# battery-select.net
KiCad netlist of a schematic drawn in Altium Designer
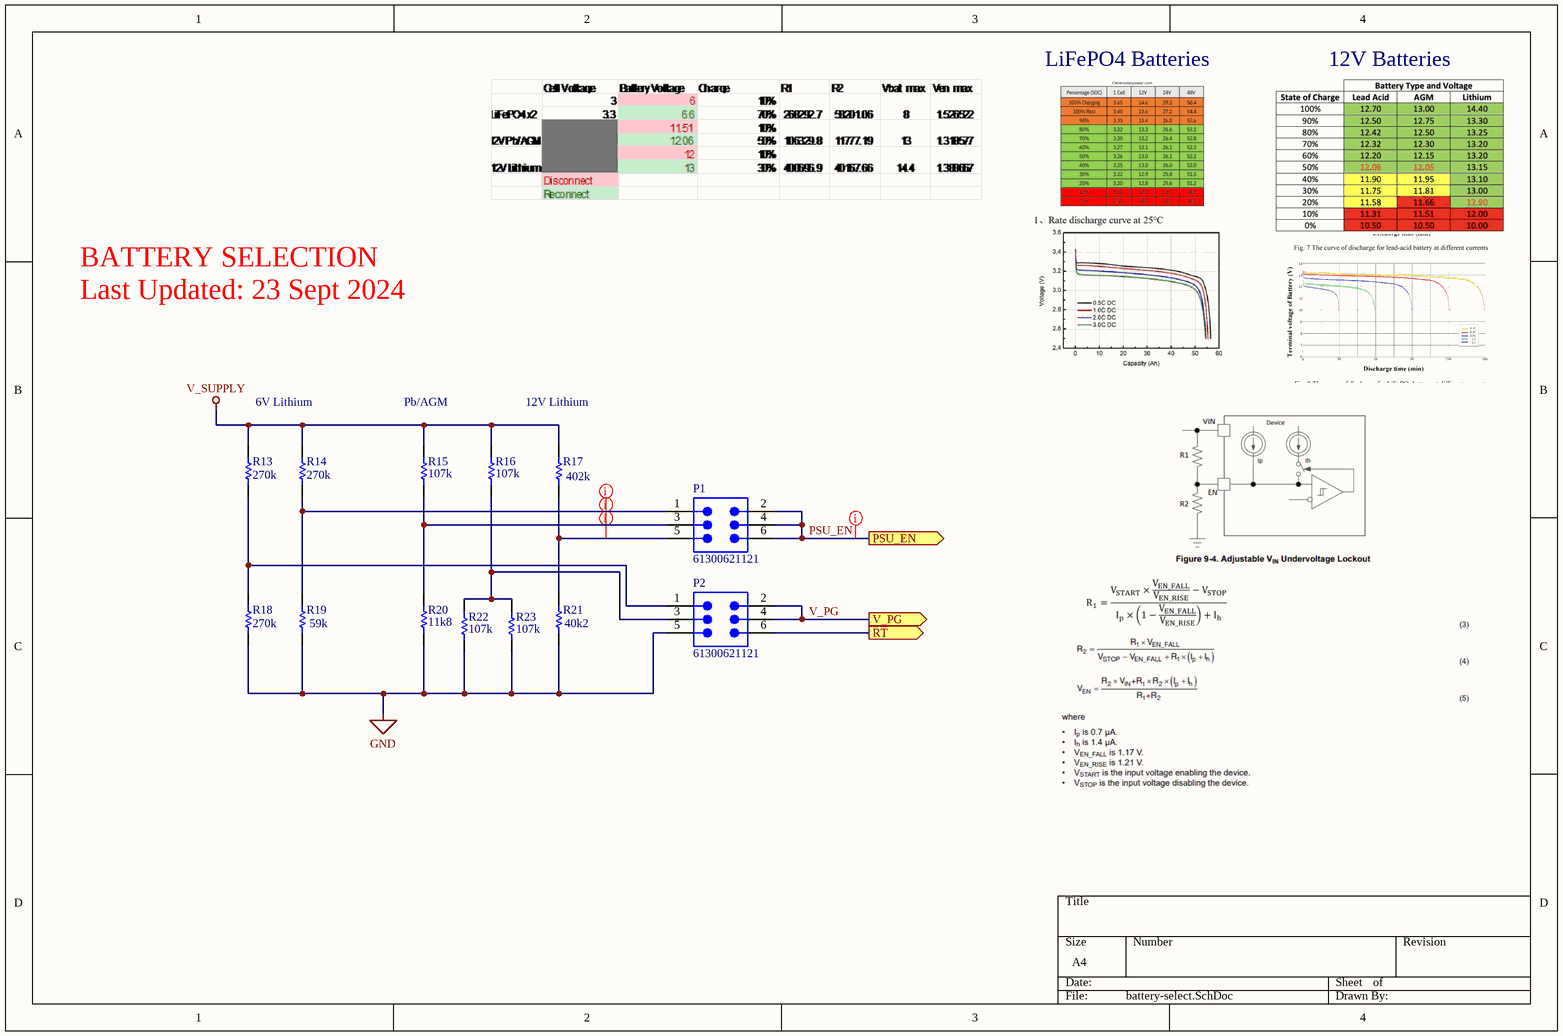
[diagram p0: battery-select.SchDoc]

(export (version "E")
  (design (tool "Eeschema 10.0.6"))
  (components
    (comp (ref "P1")
      (value "61300621121")
      (footprint "61300621121")
      (libsource (lib "Camosun College") (part "Header_Male_2R_06P"))
    )
    (comp (ref "P2")
      (value "61300621121")
      (footprint "61300621121")
      (libsource (lib "Camosun College") (part "Header_Male_2R_06P"))
    )
    (comp (ref "R13")
      (value "270k")
      (footprint "RESC2013X70X40LL20T20")
      (fields (field (name "PART NUMBER") "ERJ6ENF2703V") (field (name "MANUFACTURER") "Panasonic"))
      (libsource (lib "Altium Content Vault") (part "RES"))
    )
    (comp (ref "R14")
      (value "270k")
      (footprint "RESC2013X70X40LL20T20")
      (fields (field (name "PART NUMBER") "ERJ6ENF2703V") (field (name "MANUFACTURER") "Panasonic"))
      (libsource (lib "Altium Content Vault") (part "RES"))
    )
    (comp (ref "R15")
      (value "107k")
      (footprint "RESC2013X70X40LL20T20")
      (fields (field (name "MANUFACTURER") "Panasonic") (field (name "PART NUMBER") "ERJ-6ENF1073V"))
      (libsource (lib "Altium Content Vault") (part "RES"))
    )
    (comp (ref "R16")
      (value "107k")
      (footprint "RESC2013X70X40LL20T20")
      (fields (field (name "MANUFACTURER") "Panasonic") (field (name "PART NUMBER") "ERJ-6ENF1073V"))
      (libsource (lib "Altium Content Vault") (part "RES"))
    )
    (comp (ref "R17")
      (value "402k")
      (footprint "RESC2013X70X40LL20T20")
      (fields (field (name "PART NUMBER") "ERJ-6ENF4023V") (field (name "MANUFACTURER") "Panasonic"))
      (libsource (lib "Altium Content Vault") (part "RES"))
    )
    (comp (ref "R18")
      (value "270k")
      (footprint "RESC2013X70X40LL20T20")
      (fields (field (name "PART NUMBER") "ERJ6ENF2703V") (field (name "MANUFACTURER") "Panasonic"))
      (libsource (lib "Altium Content Vault") (part "RES"))
    )
    (comp (ref "R19")
      (value "59k")
      (footprint "RESC2013X70X40LL20T20")
      (fields (field (name "MANUFACTURER") "Panasonic") (field (name "PART NUMBER") "ERJ-6ENF5902V"))
      (libsource (lib "Altium Content Vault") (part "RES"))
    )
    (comp (ref "R20")
      (value "11k8")
      (footprint "RESC2013X70X40LL20T20")
      (fields (field (name "PART NUMBER") "ERJ-6ENF1182V") (field (name "MANUFACTURER") "Panasonic"))
      (libsource (lib "Altium Content Vault") (part "RES"))
    )
    (comp (ref "R21")
      (value "40k2")
      (footprint "RESC2013X70X40LL20T20")
      (fields (field (name "MANUFACTURER") "Panasonic") (field (name "PART NUMBER") "ERJ-6ENF4022V"))
      (libsource (lib "Altium Content Vault") (part "RES"))
    )
    (comp (ref "R22")
      (value "107k")
      (footprint "RESC2013X70X40LL20T20")
      (fields (field (name "MANUFACTURER") "Panasonic") (field (name "PART NUMBER") "ERJ-6ENF1073V"))
      (libsource (lib "Altium Content Vault") (part "RES"))
    )
    (comp (ref "R23")
      (value "107k")
      (footprint "RESC2013X70X40LL20T20")
      (fields (field (name "MANUFACTURER") "Panasonic") (field (name "PART NUMBER") "ERJ-6ENF1073V"))
      (libsource (lib "Altium Content Vault") (part "RES"))
    )
  )
  (nets
    (net (code "1") (name "/PSU_EN") (class "Default")
      (node (ref "P1") (pin "2") (pinfunction "2_2") (pintype "passive"))
      (node (ref "P1") (pin "4") (pinfunction "4_4") (pintype "passive"))
      (node (ref "P1") (pin "6") (pinfunction "6_6") (pintype "passive"))
    )
    (net (code "2") (name "/RT") (class "Default")
      (node (ref "P2") (pin "6") (pinfunction "6_6") (pintype "passive"))
    )
    (net (code "3") (name "/V_PG") (class "Default")
      (node (ref "P2") (pin "2") (pinfunction "2_2") (pintype "passive"))
      (node (ref "P2") (pin "4") (pinfunction "4_4") (pintype "passive"))
    )
    (net (code "4") (name "GND") (class "Default")
      (node (ref "P2") (pin "5") (pinfunction "5_5") (pintype "passive"))
      (node (ref "R18") (pin "1") (pinfunction "1_1") (pintype "passive"))
      (node (ref "R19") (pin "1") (pinfunction "1_1") (pintype "passive"))
      (node (ref "R20") (pin "1") (pinfunction "1_1") (pintype "passive"))
      (node (ref "R21") (pin "1") (pinfunction "1_1") (pintype "passive"))
      (node (ref "R22") (pin "1") (pinfunction "1_1") (pintype "passive"))
      (node (ref "R23") (pin "1") (pinfunction "1_1") (pintype "passive"))
    )
    (net (code "5") (name "Net-(P1-Pad1)") (class "Default")
      (node (ref "P1") (pin "1") (pinfunction "1_1") (pintype "passive"))
      (node (ref "R14") (pin "1") (pinfunction "1_1") (pintype "passive"))
      (node (ref "R19") (pin "2") (pinfunction "2_2") (pintype "passive"))
    )
    (net (code "6") (name "Net-(P1-Pad3)") (class "Default")
      (node (ref "P1") (pin "3") (pinfunction "3_3") (pintype "passive"))
      (node (ref "R15") (pin "1") (pinfunction "1_1") (pintype "passive"))
      (node (ref "R20") (pin "2") (pinfunction "2_2") (pintype "passive"))
    )
    (net (code "7") (name "Net-(P1-Pad5)") (class "Default")
      (node (ref "P1") (pin "5") (pinfunction "5_5") (pintype "passive"))
      (node (ref "R17") (pin "1") (pinfunction "1_1") (pintype "passive"))
      (node (ref "R21") (pin "2") (pinfunction "2_2") (pintype "passive"))
    )
    (net (code "8") (name "Net-(P2-Pad1)") (class "Default")
      (node (ref "P2") (pin "1") (pinfunction "1_1") (pintype "passive"))
      (node (ref "R13") (pin "1") (pinfunction "1_1") (pintype "passive"))
      (node (ref "R18") (pin "2") (pinfunction "2_2") (pintype "passive"))
    )
    (net (code "9") (name "Net-(P2-Pad3)") (class "Default")
      (node (ref "P2") (pin "3") (pinfunction "3_3") (pintype "passive"))
      (node (ref "R16") (pin "1") (pinfunction "1_1") (pintype "passive"))
      (node (ref "R22") (pin "2") (pinfunction "2_2") (pintype "passive"))
      (node (ref "R23") (pin "2") (pinfunction "2_2") (pintype "passive"))
    )
    (net (code "10") (name "V_SUPPLY") (class "Default")
      (node (ref "R13") (pin "2") (pinfunction "2_2") (pintype "passive"))
      (node (ref "R14") (pin "2") (pinfunction "2_2") (pintype "passive"))
      (node (ref "R15") (pin "2") (pinfunction "2_2") (pintype "passive"))
      (node (ref "R16") (pin "2") (pinfunction "2_2") (pintype "passive"))
      (node (ref "R17") (pin "2") (pinfunction "2_2") (pintype "passive"))
    )
  )
)
